# preamp.net
KiCad netlist of a schematic drawn in EAGLE
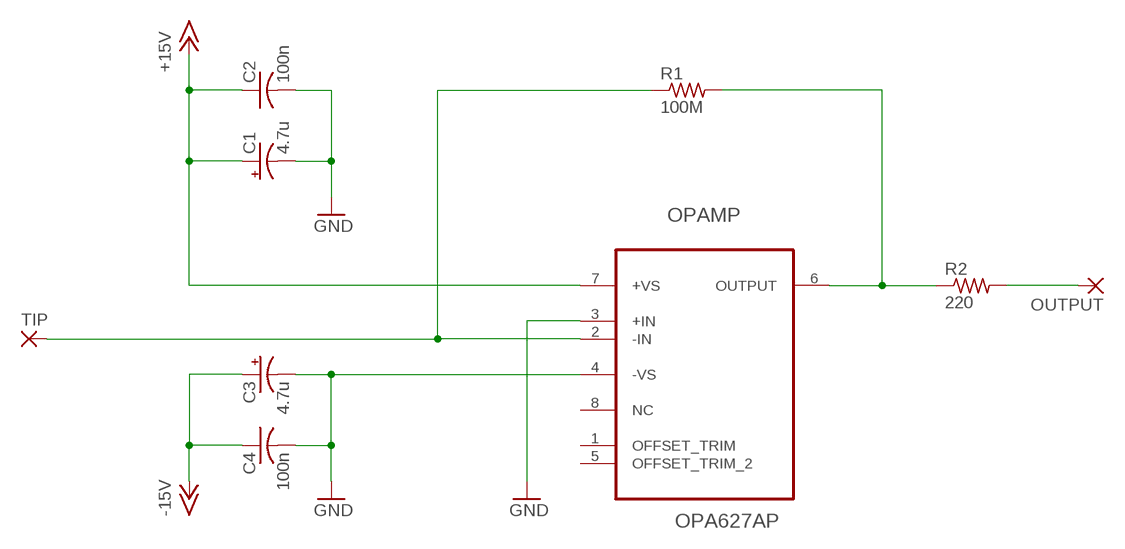
[diagram p0: schematic, sheet 1]

(export (version "E")
  (design (tool "Eeschema 10.0.6"))
  (components
    (comp (ref "C1")
      (value "4.7u")
      (footprint "eagle-import:E15-6")
      (libsource (lib "eagle-import") (part "CPOL-USE15-6AXIAL"))
    )
    (comp (ref "C2")
      (value "100n")
      (footprint "eagle-import:C050-050X075")
      (libsource (lib "eagle-import") (part "C-US050-050X075"))
    )
    (comp (ref "C3")
      (value "4.7u")
      (footprint "eagle-import:E15-6")
      (libsource (lib "eagle-import") (part "CPOL-USE15-6AXIAL"))
    )
    (comp (ref "C4")
      (value "100n")
      (footprint "eagle-import:C050-050X075")
      (libsource (lib "eagle-import") (part "C-US050-050X075"))
    )
    (comp (ref "OPAMP")
      (value "OPA627AP")
      (footprint "eagle-import:DIP254P762X508-8")
      (libsource (lib "eagle-import") (part "OPA627AP"))
    )
    (comp (ref "OUTPUT")
      (value "1,6/0,8")
      (footprint "eagle-import:1,6_0,8")
      (libsource (lib "eagle-import") (part "1,6/0,8"))
    )
    (comp (ref "R1")
      (value "100M")
      (footprint "eagle-import:0204_7")
      (libsource (lib "eagle-import") (part "R-US_0204/7"))
    )
    (comp (ref "R2")
      (value "220")
      (footprint "eagle-import:0204_7")
      (libsource (lib "eagle-import") (part "R-US_0204/7"))
    )
    (comp (ref "TIP")
      (value "1,6/0,8")
      (footprint "eagle-import:1,6_0,8")
      (libsource (lib "eagle-import") (part "1,6/0,8"))
    )
  )
  (nets
    (net (code "1") (name "+15V") (class "Default")
      (node (ref "C1") (pin "+") (pinfunction "+_+") (pintype "passive"))
      (node (ref "C2") (pin "1") (pinfunction "1_1") (pintype "passive"))
      (node (ref "OPAMP") (pin "7") (pinfunction "+VS_7") (pintype "power_in"))
    )
    (net (code "2") (name "-15V") (class "Default")
      (node (ref "C3") (pin "+") (pinfunction "+_+") (pintype "passive"))
      (node (ref "C4") (pin "1") (pinfunction "1_1") (pintype "passive"))
    )
    (net (code "3") (name "GND") (class "Default")
      (node (ref "C1") (pin "-") (pinfunction "-_-") (pintype "passive"))
      (node (ref "C2") (pin "2") (pinfunction "2_2") (pintype "passive"))
      (node (ref "C3") (pin "-") (pinfunction "-_-") (pintype "passive"))
      (node (ref "C4") (pin "2") (pinfunction "2_2") (pintype "passive"))
      (node (ref "OPAMP") (pin "3") (pinfunction "+IN_3") (pintype "input"))
      (node (ref "OPAMP") (pin "4") (pinfunction "-VS_4") (pintype "power_in"))
    )
    (net (code "4") (name "Net-(OPAMP--IN)") (class "Default")
      (node (ref "OPAMP") (pin "2") (pinfunction "-IN_2") (pintype "input"))
      (node (ref "R1") (pin "1") (pinfunction "1_1") (pintype "passive"))
      (node (ref "TIP") (pin "1") (pinfunction "P_1") (pintype "passive"))
    )
    (net (code "5") (name "Net-(OPAMP-OUTPUT)") (class "Default")
      (node (ref "OPAMP") (pin "6") (pinfunction "OUTPUT_6") (pintype "output"))
      (node (ref "R1") (pin "2") (pinfunction "2_2") (pintype "passive"))
      (node (ref "R2") (pin "1") (pinfunction "1_1") (pintype "passive"))
    )
    (net (code "6") (name "Net-(OUTPUT-P)") (class "Default")
      (node (ref "OUTPUT") (pin "1") (pinfunction "P_1") (pintype "passive"))
      (node (ref "R2") (pin "2") (pinfunction "2_2") (pintype "passive"))
    )
    (net (code "7") (name "unconnected-(OPAMP-NC-Pad8)") (class "Default")
      (node (ref "OPAMP") (pin "8") (pinfunction "NC_8") (pintype "no_connect"))
    )
    (net (code "8") (name "unconnected-(OPAMP-OFFSET_TRIM-Pad1)") (class "Default")
      (node (ref "OPAMP") (pin "1") (pinfunction "OFFSET_TRIM_1") (pintype "passive"))
    )
    (net (code "9") (name "unconnected-(OPAMP-OFFSET_TRIM_2-Pad5)") (class "Default")
      (node (ref "OPAMP") (pin "5") (pinfunction "OFFSET_TRIM_2_5") (pintype "passive"))
    )
  )
)
